# DIPBreakout.net
KiCad netlist of a schematic drawn in Altium Designer
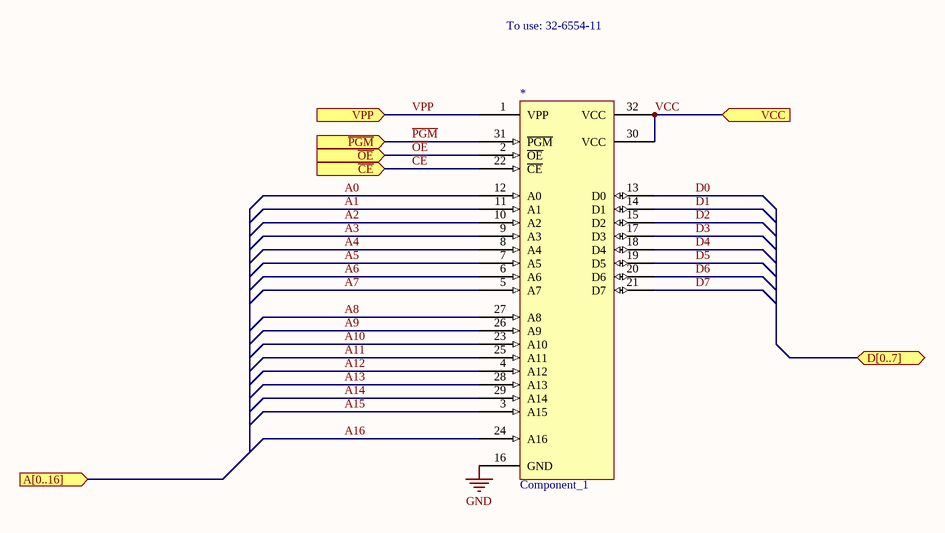
[diagram p0: DIPBreakout.SchDoc]

(export (version "E")
  (design (tool "Eeschema 10.0.6"))
  (components
    (comp (ref "*")
      (value "Component_1")
      (footprint "PCBComponent_1")
      (libsource (lib "32-6554-11") (part "Component_1"))
    )
  )
  (nets
    (net (code "1") (name "/A0") (class "Default")
      (node (ref "*") (pin "12") (pinfunction "A0_12") (pintype "input"))
    )
    (net (code "2") (name "/A1") (class "Default")
      (node (ref "*") (pin "11") (pinfunction "A1_11") (pintype "input"))
    )
    (net (code "3") (name "/A2") (class "Default")
      (node (ref "*") (pin "10") (pinfunction "A2_10") (pintype "input"))
    )
    (net (code "4") (name "/A3") (class "Default")
      (node (ref "*") (pin "9") (pinfunction "A3_9") (pintype "input"))
    )
    (net (code "5") (name "/A4") (class "Default")
      (node (ref "*") (pin "8") (pinfunction "A4_8") (pintype "input"))
    )
    (net (code "6") (name "/A5") (class "Default")
      (node (ref "*") (pin "7") (pinfunction "A5_7") (pintype "input"))
    )
    (net (code "7") (name "/A6") (class "Default")
      (node (ref "*") (pin "6") (pinfunction "A6_6") (pintype "input"))
    )
    (net (code "8") (name "/A7") (class "Default")
      (node (ref "*") (pin "5") (pinfunction "A7_5") (pintype "input"))
    )
    (net (code "9") (name "/A8") (class "Default")
      (node (ref "*") (pin "27") (pinfunction "A8_27") (pintype "input"))
    )
    (net (code "10") (name "/A9") (class "Default")
      (node (ref "*") (pin "26") (pinfunction "A9_26") (pintype "input"))
    )
    (net (code "11") (name "/A10") (class "Default")
      (node (ref "*") (pin "23") (pinfunction "A10_23") (pintype "input"))
    )
    (net (code "12") (name "/A11") (class "Default")
      (node (ref "*") (pin "25") (pinfunction "A11_25") (pintype "input"))
    )
    (net (code "13") (name "/A12") (class "Default")
      (node (ref "*") (pin "4") (pinfunction "A12_4") (pintype "input"))
    )
    (net (code "14") (name "/A13") (class "Default")
      (node (ref "*") (pin "28") (pinfunction "A13_28") (pintype "input"))
    )
    (net (code "15") (name "/A14") (class "Default")
      (node (ref "*") (pin "29") (pinfunction "A14_29") (pintype "input"))
    )
    (net (code "16") (name "/A15") (class "Default")
      (node (ref "*") (pin "3") (pinfunction "A15_3") (pintype "input"))
    )
    (net (code "17") (name "/A16") (class "Default")
      (node (ref "*") (pin "24") (pinfunction "A16_24") (pintype "input"))
    )
    (net (code "19") (name "/D0") (class "Default")
      (node (ref "*") (pin "13") (pinfunction "D0_13") (pintype "bidirectional"))
    )
    (net (code "20") (name "/D1") (class "Default")
      (node (ref "*") (pin "14") (pinfunction "D1_14") (pintype "bidirectional"))
    )
    (net (code "21") (name "/D2") (class "Default")
      (node (ref "*") (pin "15") (pinfunction "D2_15") (pintype "bidirectional"))
    )
    (net (code "22") (name "/D3") (class "Default")
      (node (ref "*") (pin "17") (pinfunction "D3_17") (pintype "bidirectional"))
    )
    (net (code "23") (name "/D4") (class "Default")
      (node (ref "*") (pin "18") (pinfunction "D4_18") (pintype "bidirectional"))
    )
    (net (code "24") (name "/D5") (class "Default")
      (node (ref "*") (pin "19") (pinfunction "D5_19") (pintype "bidirectional"))
    )
    (net (code "25") (name "/D6") (class "Default")
      (node (ref "*") (pin "20") (pinfunction "D6_20") (pintype "bidirectional"))
    )
    (net (code "26") (name "/D7") (class "Default")
      (node (ref "*") (pin "21") (pinfunction "D7_21") (pintype "bidirectional"))
    )
    (net (code "28") (name "/VCC") (class "Default")
      (node (ref "*") (pin "30") (pinfunction "VCC_30") (pintype "power_in"))
      (node (ref "*") (pin "32") (pinfunction "VCC_32") (pintype "power_in"))
    )
    (net (code "29") (name "/VPP") (class "Default")
      (node (ref "*") (pin "1") (pinfunction "VPP_1") (pintype "power_in"))
    )
    (net (code "30") (name "/~{CE}") (class "Default")
      (node (ref "*") (pin "22") (pinfunction "~{CE}_22") (pintype "input"))
    )
    (net (code "31") (name "/~{OE}") (class "Default")
      (node (ref "*") (pin "2") (pinfunction "~{OE}_2") (pintype "input"))
    )
    (net (code "32") (name "/~{PGM}") (class "Default")
      (node (ref "*") (pin "31") (pinfunction "~{PGM}_31") (pintype "input"))
    )
    (net (code "33") (name "GND") (class "Default")
      (node (ref "*") (pin "16") (pinfunction "GND_16") (pintype "power_in"))
    )
  )
)
